# contbrd.net
KiCad netlist of a schematic drawn in EAGLE
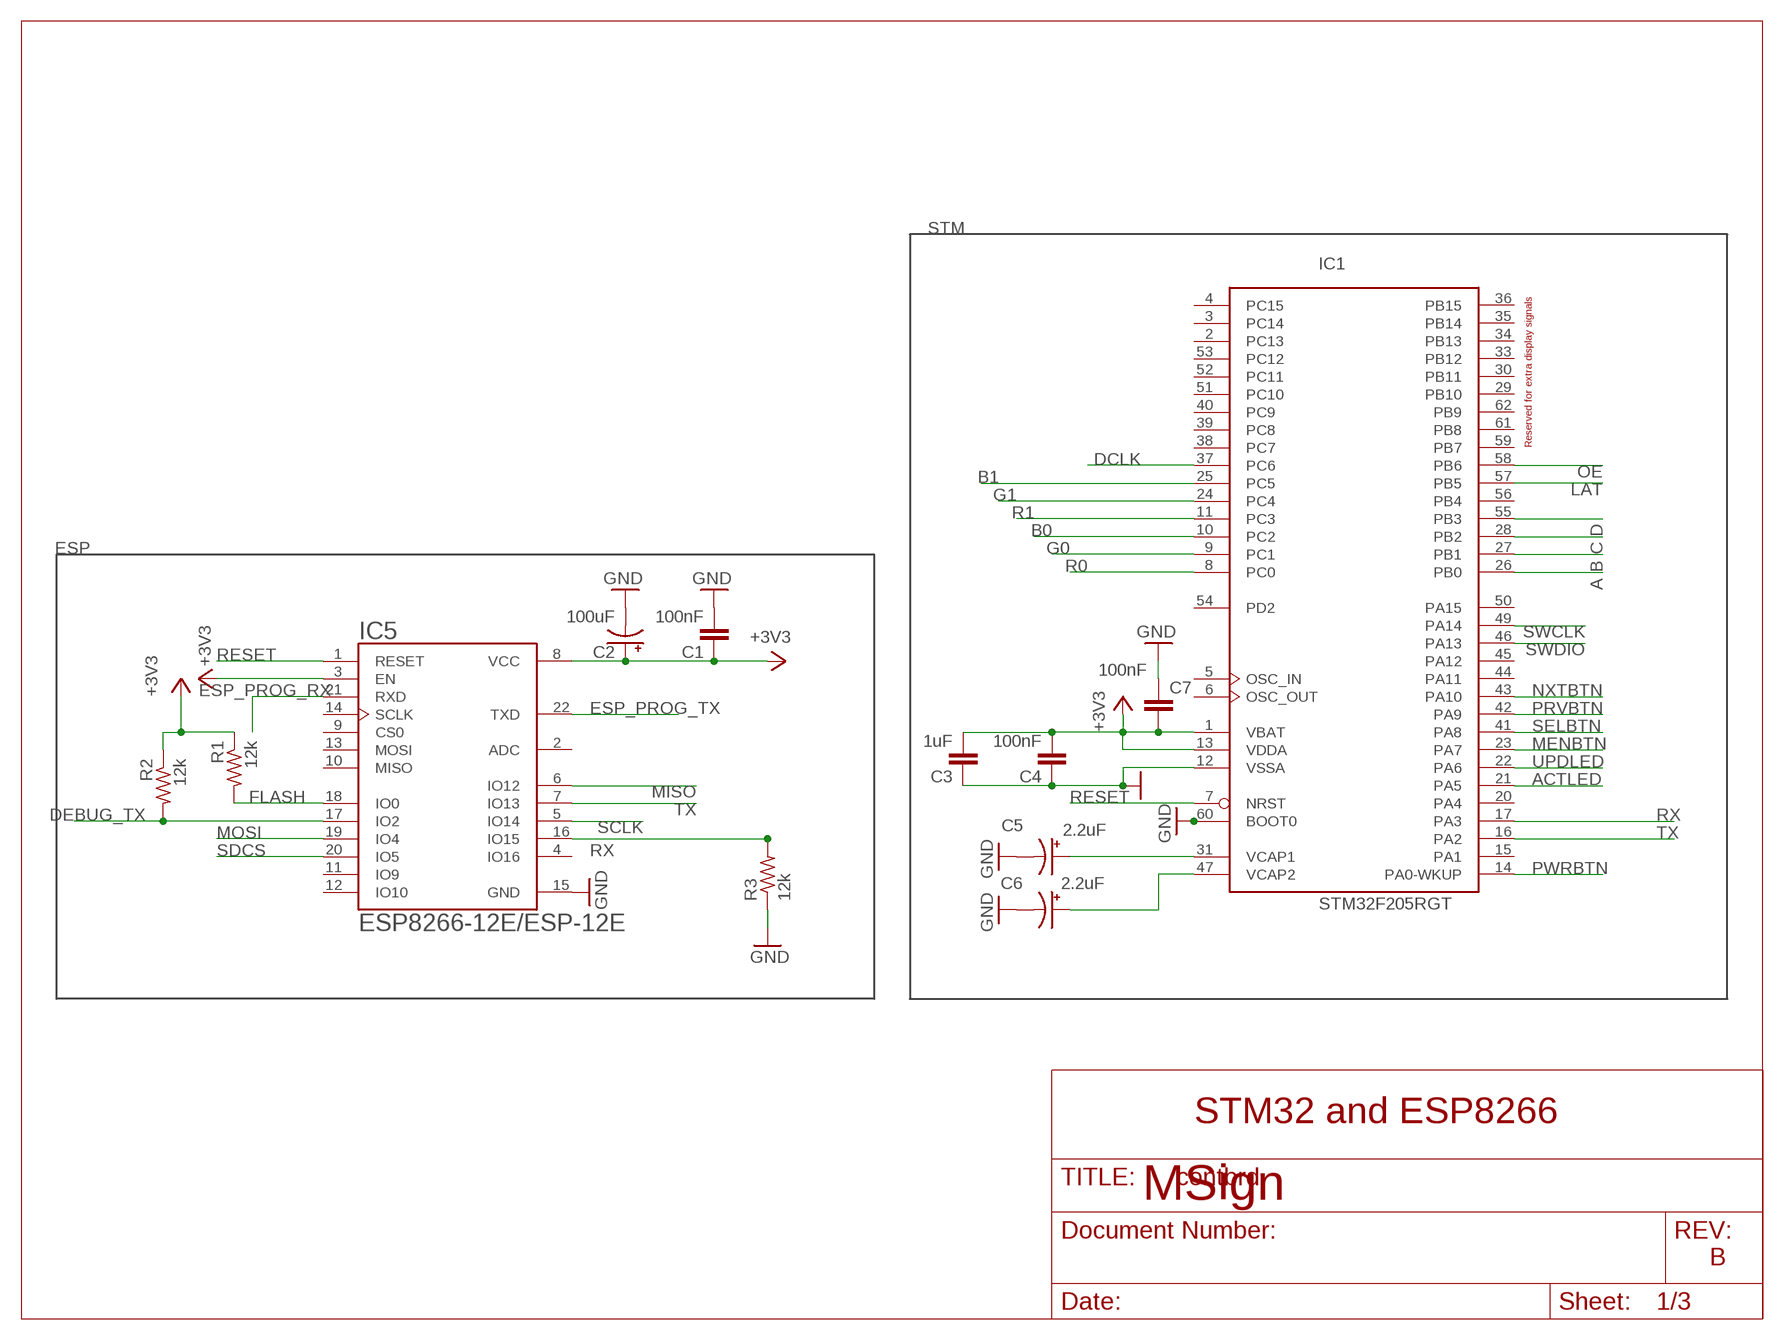
[diagram p0: schematic, sheet 1]
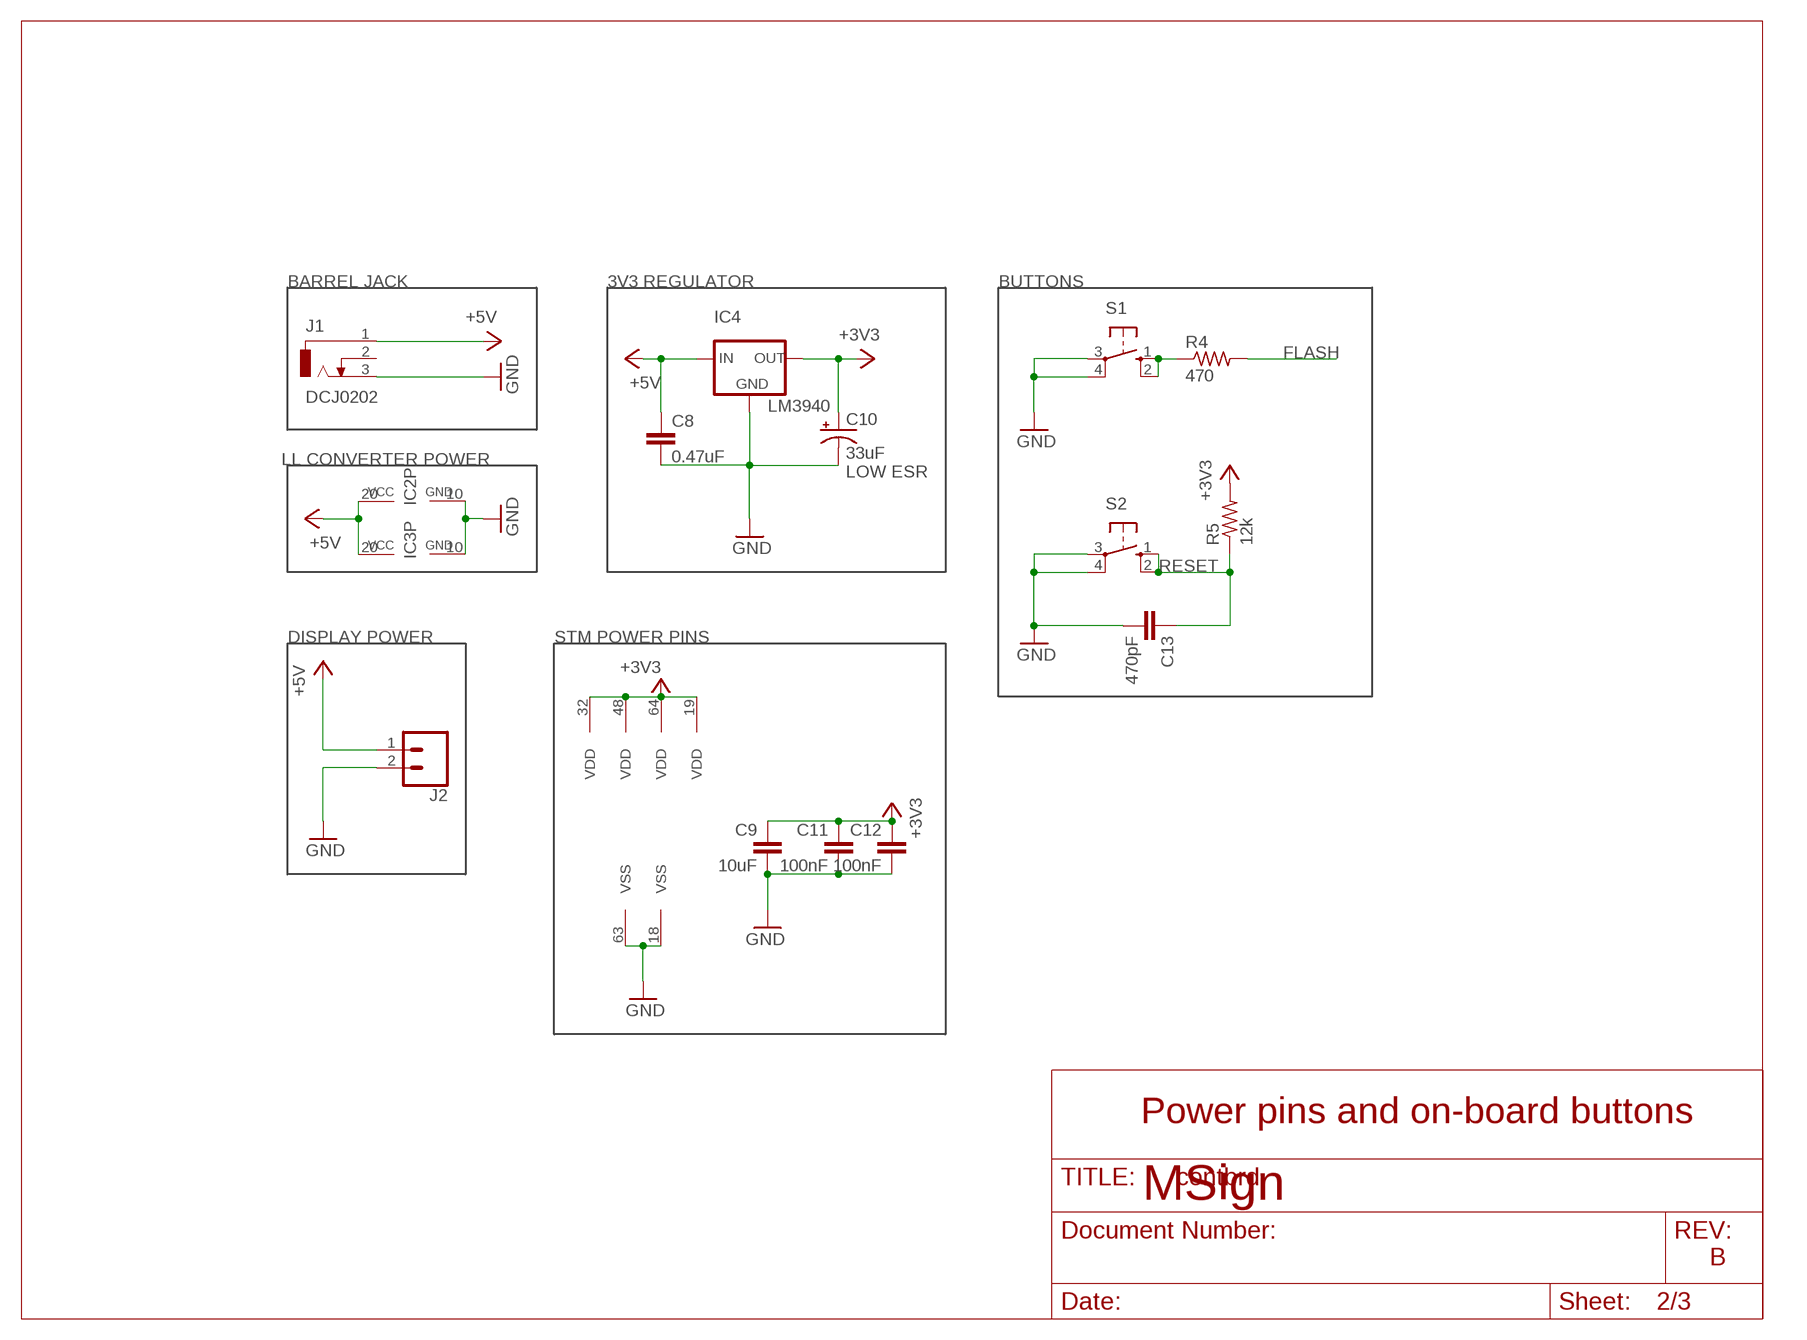
[diagram p1: schematic, sheet 2]
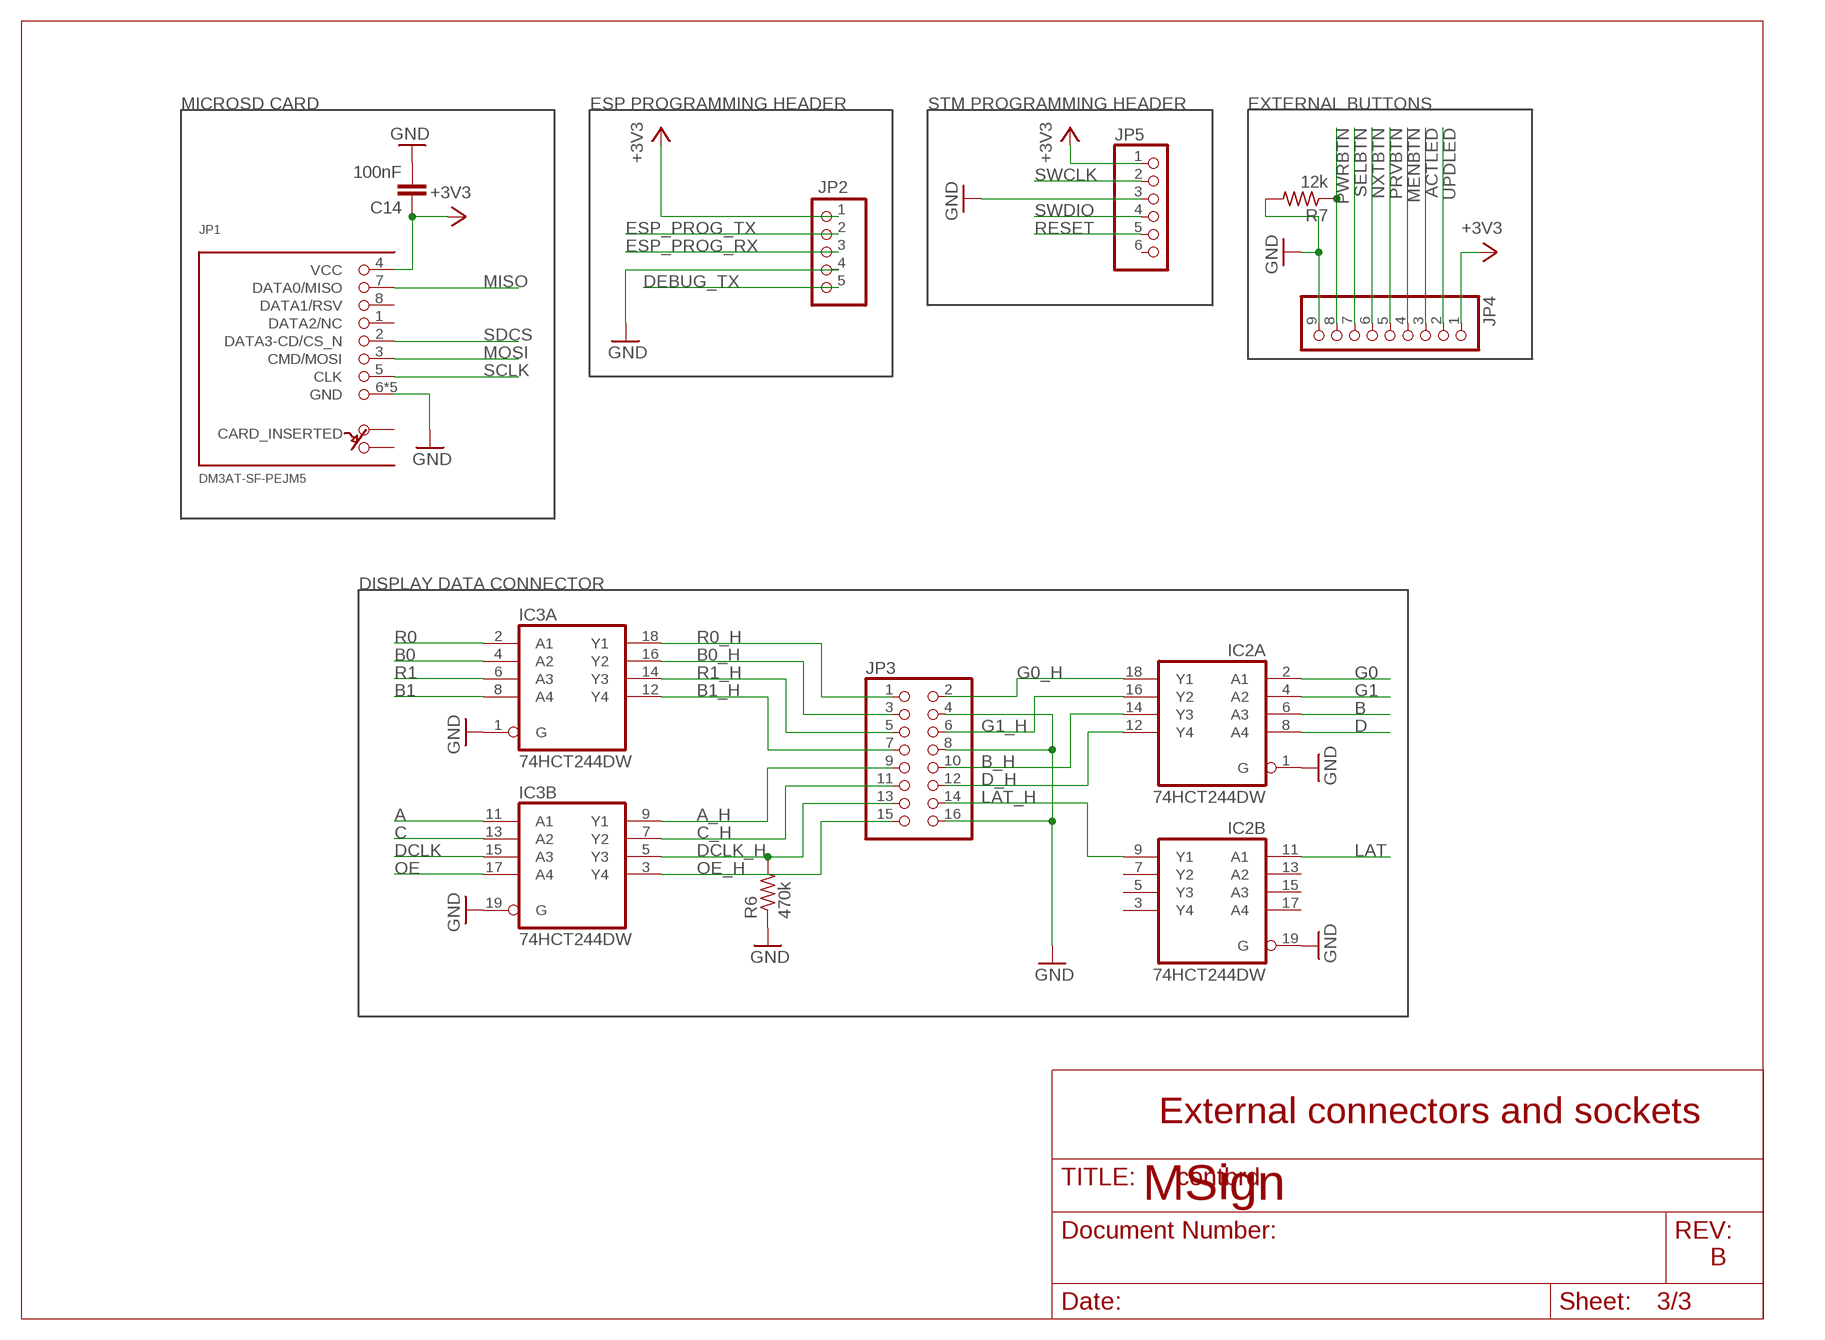
[diagram p2: schematic, sheet 3]

(export (version "E")
  (design (tool "Eeschema 10.0.6"))
  (components
    (comp (ref "C14")
      (value "100nF")
      (footprint "eagle-import:C025-025X050")
      (libsource (lib "eagle-import") (part "C-EU025-025X050"))
    )
    (comp (ref "IC2")
      (value "74HCT244DW")
      (footprint "eagle-import:SO20W")
      (libsource (lib "eagle-import") (part "74244DWHCT"))
    )
    (comp (ref "IC3")
      (value "74HCT244DW")
      (footprint "eagle-import:SO20W")
      (libsource (lib "eagle-import") (part "74244DWHCT"))
    )
    (comp (ref "JP1")
      (value "DM3AT-SF-PEJM5")
      (footprint "eagle-import:DM3AT-SF-PEJM5")
      (fields (field (name "MANUFACTURER") "Hirose Electric Co Ltd"))
      (libsource (lib "eagle-import") (part "DM3AT-SF-PEJM5"))
    )
    (comp (ref "JP2")
      (value "PINHD-1X5")
      (footprint "eagle-import:1X05")
      (libsource (lib "eagle-import") (part "PINHD-1X5"))
    )
    (comp (ref "JP3")
      (value "PINHD-2X8")
      (footprint "eagle-import:2X08")
      (libsource (lib "eagle-import") (part "PINHD-2X8"))
    )
    (comp (ref "JP4")
      (value "PINHD-1X9")
      (footprint "eagle-import:1X09")
      (libsource (lib "eagle-import") (part "PINHD-1X9"))
    )
    (comp (ref "JP5")
      (value "PINHD-1X6")
      (footprint "eagle-import:1X06")
      (libsource (lib "eagle-import") (part "PINHD-1X6"))
    )
    (comp (ref "R6")
      (value "470k")
      (footprint "eagle-import:0204_7")
      (libsource (lib "eagle-import") (part "R-US_0204/7"))
    )
    (comp (ref "R7")
      (value "12k")
      (footprint "eagle-import:0204_7")
      (libsource (lib "eagle-import") (part "R-US_0204/7"))
    )
    (comp (ref "C8")
      (value "0.47uF")
      (footprint "eagle-import:C050-024X044")
      (libsource (lib "eagle-import") (part "C-EU050-024X044"))
    )
    (comp (ref "C9")
      (value "10uF")
      (footprint "eagle-import:C025-025X050")
      (libsource (lib "eagle-import") (part "C-EU025-025X050"))
    )
    (comp (ref "C10")
      (value "33uF")
      (footprint "eagle-import:E2-5")
      (libsource (lib "eagle-import") (part "CPOL-USE2-5"))
    )
    (comp (ref "C11")
      (value "100nF")
      (footprint "eagle-import:C025-025X050")
      (libsource (lib "eagle-import") (part "C-EU025-025X050"))
    )
    (comp (ref "C12")
      (value "100nF")
      (footprint "eagle-import:C025-025X050")
      (libsource (lib "eagle-import") (part "C-EU025-025X050"))
    )
    (comp (ref "C13")
      (value "470pF")
      (footprint "eagle-import:C025-025X050")
      (libsource (lib "eagle-import") (part "C-EU025-025X050"))
    )
    (comp (ref "IC1")
      (value "STM32F205RGT")
      (footprint "eagle-import:LQFP64")
      (libsource (lib "eagle-import") (part "STM32F205RTG"))
    )
    (comp (ref "IC4")
      (value "LM3940")
      (footprint "eagle-import:TO220")
      (fields (field (name "MF") "Texas Instruments"))
      (libsource (lib "eagle-import") (part "LM3940"))
    )
    (comp (ref "J1")
      (value "DCJ0202")
      (footprint "eagle-import:DCJ0202")
      (libsource (lib "eagle-import") (part "DCJ0202"))
    )
    (comp (ref "J2")
      (value "CONN_025MM")
      (footprint "eagle-import:SCREWTERMINAL-5MM-2")
      (libsource (lib "eagle-import") (part "CONN_025MM"))
    )
    (comp (ref "R4")
      (value "470")
      (footprint "eagle-import:0204_7")
      (libsource (lib "eagle-import") (part "R-US_0204/7"))
    )
    (comp (ref "R5")
      (value "12k")
      (footprint "eagle-import:0204_7")
      (libsource (lib "eagle-import") (part "R-US_0204/7"))
    )
    (comp (ref "S1")
      (value "10-XX")
      (footprint "eagle-import:B3F-10XX")
      (fields (field (name "MPN") "B3F-1000"))
      (libsource (lib "eagle-import") (part "10-XX"))
    )
    (comp (ref "S2")
      (value "10-XX")
      (footprint "eagle-import:B3F-10XX")
      (fields (field (name "MPN") "B3F-1000"))
      (libsource (lib "eagle-import") (part "10-XX"))
    )
    (comp (ref "C1")
      (value "100nF")
      (footprint "eagle-import:C025-025X050")
      (libsource (lib "eagle-import") (part "C-EU025-025X050"))
    )
    (comp (ref "C2")
      (value "100uF")
      (footprint "eagle-import:E2,5-6")
      (libsource (lib "eagle-import") (part "CPOL-USE2.5-6"))
    )
    (comp (ref "C3")
      (value "1uF")
      (footprint "eagle-import:C050-024X044")
      (libsource (lib "eagle-import") (part "C-EU050-024X044"))
    )
    (comp (ref "C4")
      (value "100nF")
      (footprint "eagle-import:C025-025X050")
      (libsource (lib "eagle-import") (part "C-EU025-025X050"))
    )
    (comp (ref "C5")
      (value "2.2uF")
      (footprint "eagle-import:E1,8-4")
      (libsource (lib "eagle-import") (part "CPOL-USE1.8-4"))
    )
    (comp (ref "C6")
      (value "2.2uF")
      (footprint "eagle-import:E1,8-4")
      (libsource (lib "eagle-import") (part "CPOL-USE1.8-4"))
    )
    (comp (ref "C7")
      (value "100nF")
      (footprint "eagle-import:C025-025X050")
      (libsource (lib "eagle-import") (part "C-EU025-025X050"))
    )
    (comp (ref "IC5")
      (value "ESP8266-12E/ESP-12E")
      (footprint "eagle-import:XCVR_ESP8266-12E_ESP-12E")
      (fields (field (name "MF") "AI-Thinker"))
      (libsource (lib "eagle-import") (part "ESP8266-12E/ESP-12E"))
    )
    (comp (ref "R1")
      (value "12k")
      (footprint "eagle-import:0204_7")
      (libsource (lib "eagle-import") (part "R-US_0204/7"))
    )
    (comp (ref "R2")
      (value "12k")
      (footprint "eagle-import:0204_7")
      (libsource (lib "eagle-import") (part "R-US_0204/7"))
    )
    (comp (ref "R3")
      (value "12k")
      (footprint "eagle-import:0204_7")
      (libsource (lib "eagle-import") (part "R-US_0204/7"))
    )
  )
  (nets
    (net (code "1") (name "+3V3") (class "Default")
      (node (ref "C1") (pin "1") (pinfunction "1_1") (pintype "passive"))
      (node (ref "C10") (pin "+") (pinfunction "+_+") (pintype "passive"))
      (node (ref "C11") (pin "1") (pinfunction "1_1") (pintype "passive"))
      (node (ref "C12") (pin "1") (pinfunction "1_1") (pintype "passive"))
      (node (ref "C14") (pin "1") (pinfunction "1_1") (pintype "passive"))
      (node (ref "C2") (pin "+") (pinfunction "+_+") (pintype "passive"))
      (node (ref "C3") (pin "2") (pinfunction "2_2") (pintype "passive"))
      (node (ref "C4") (pin "2") (pinfunction "2_2") (pintype "passive"))
      (node (ref "C7") (pin "2") (pinfunction "2_2") (pintype "passive"))
      (node (ref "C9") (pin "1") (pinfunction "1_1") (pintype "passive"))
      (node (ref "IC1") (pin "1") (pinfunction "VBAT_1") (pintype "power_in"))
      (node (ref "IC1") (pin "13") (pinfunction "VDDA_13") (pintype "power_in"))
      (node (ref "IC1") (pin "19") (pinfunction "VDD_19") (pintype "power_in"))
      (node (ref "IC1") (pin "32") (pinfunction "VDD_32") (pintype "power_in"))
      (node (ref "IC1") (pin "48") (pinfunction "VDD_48") (pintype "power_in"))
      (node (ref "IC1") (pin "64") (pinfunction "VDD_64") (pintype "power_in"))
      (node (ref "IC4") (pin "3") (pinfunction "OUT_3") (pintype "output"))
      (node (ref "IC5") (pin "3") (pinfunction "EN_3") (pintype "input"))
      (node (ref "IC5") (pin "8") (pinfunction "VCC_8") (pintype "power_in"))
      (node (ref "JP1") (pin "4") (pinfunction "VCC_4") (pintype "bidirectional"))
      (node (ref "JP2") (pin "1") (pinfunction "1_1") (pintype "passive"))
      (node (ref "JP4") (pin "1") (pinfunction "1_1") (pintype "passive"))
      (node (ref "JP5") (pin "1") (pinfunction "1_1") (pintype "passive"))
      (node (ref "R1") (pin "1") (pinfunction "1_1") (pintype "passive"))
      (node (ref "R2") (pin "1") (pinfunction "1_1") (pintype "passive"))
      (node (ref "R5") (pin "2") (pinfunction "2_2") (pintype "passive"))
    )
    (net (code "2") (name "+5V") (class "Default")
      (node (ref "C8") (pin "1") (pinfunction "1_1") (pintype "passive"))
      (node (ref "IC2") (pin "20") (pinfunction "VCC_20") (pintype "power_in"))
      (node (ref "IC3") (pin "20") (pinfunction "VCC_20") (pintype "power_in"))
      (node (ref "IC4") (pin "1") (pinfunction "IN_1") (pintype "input"))
      (node (ref "J1") (pin "1") (pinfunction "1_1") (pintype "passive"))
      (node (ref "J2") (pin "1") (pinfunction "1_1") (pintype "passive"))
    )
    (net (code "3") (name "A") (class "Default")
      (node (ref "IC1") (pin "26") (pinfunction "PB0_26") (pintype "bidirectional"))
      (node (ref "IC3") (pin "11") (pinfunction "A1_11") (pintype "input"))
    )
    (net (code "4") (name "ACTLED") (class "Default")
      (node (ref "IC1") (pin "21") (pinfunction "PA5_21") (pintype "bidirectional"))
      (node (ref "JP4") (pin "3") (pinfunction "3_3") (pintype "passive"))
    )
    (net (code "5") (name "A_H") (class "Default")
      (node (ref "IC3") (pin "9") (pinfunction "Y1_9") (pintype "tri_state"))
      (node (ref "JP3") (pin "9") (pinfunction "9_9") (pintype "passive"))
    )
    (net (code "6") (name "B") (class "Default")
      (node (ref "IC1") (pin "27") (pinfunction "PB1_27") (pintype "bidirectional"))
      (node (ref "IC2") (pin "6") (pinfunction "A3_6") (pintype "input"))
    )
    (net (code "7") (name "B0") (class "Default")
      (node (ref "IC1") (pin "10") (pinfunction "PC2_10") (pintype "bidirectional"))
      (node (ref "IC3") (pin "4") (pinfunction "A2_4") (pintype "input"))
    )
    (net (code "8") (name "B0_H") (class "Default")
      (node (ref "IC3") (pin "16") (pinfunction "Y2_16") (pintype "tri_state"))
      (node (ref "JP3") (pin "3") (pinfunction "3_3") (pintype "passive"))
    )
    (net (code "9") (name "B1") (class "Default")
      (node (ref "IC1") (pin "25") (pinfunction "PC5_25") (pintype "bidirectional"))
      (node (ref "IC3") (pin "8") (pinfunction "A4_8") (pintype "input"))
    )
    (net (code "10") (name "B1_H") (class "Default")
      (node (ref "IC3") (pin "12") (pinfunction "Y4_12") (pintype "tri_state"))
      (node (ref "JP3") (pin "7") (pinfunction "7_7") (pintype "passive"))
    )
    (net (code "11") (name "B_H") (class "Default")
      (node (ref "IC2") (pin "14") (pinfunction "Y3_14") (pintype "tri_state"))
      (node (ref "JP3") (pin "10") (pinfunction "10_10") (pintype "passive"))
    )
    (net (code "12") (name "C") (class "Default")
      (node (ref "IC1") (pin "28") (pinfunction "PB2_28") (pintype "bidirectional"))
      (node (ref "IC3") (pin "13") (pinfunction "A2_13") (pintype "input"))
    )
    (net (code "13") (name "C_H") (class "Default")
      (node (ref "IC3") (pin "7") (pinfunction "Y2_7") (pintype "tri_state"))
      (node (ref "JP3") (pin "11") (pinfunction "11_11") (pintype "passive"))
    )
    (net (code "14") (name "D") (class "Default")
      (node (ref "IC1") (pin "55") (pinfunction "PB3_55") (pintype "bidirectional"))
      (node (ref "IC2") (pin "8") (pinfunction "A4_8") (pintype "input"))
    )
    (net (code "15") (name "DCLK") (class "Default")
      (node (ref "IC1") (pin "37") (pinfunction "PC6_37") (pintype "bidirectional"))
      (node (ref "IC3") (pin "15") (pinfunction "A3_15") (pintype "input"))
    )
    (net (code "16") (name "DCLK_H") (class "Default")
      (node (ref "IC3") (pin "5") (pinfunction "Y3_5") (pintype "tri_state"))
      (node (ref "JP3") (pin "13") (pinfunction "13_13") (pintype "passive"))
      (node (ref "R6") (pin "2") (pinfunction "2_2") (pintype "passive"))
    )
    (net (code "17") (name "DEBUG_TX") (class "Default")
      (node (ref "IC5") (pin "17") (pinfunction "IO2_17") (pintype "bidirectional"))
      (node (ref "JP2") (pin "5") (pinfunction "5_5") (pintype "passive"))
      (node (ref "R2") (pin "2") (pinfunction "2_2") (pintype "passive"))
    )
    (net (code "18") (name "D_H") (class "Default")
      (node (ref "IC2") (pin "12") (pinfunction "Y4_12") (pintype "tri_state"))
      (node (ref "JP3") (pin "12") (pinfunction "12_12") (pintype "passive"))
    )
    (net (code "19") (name "ESP_PROG_RX") (class "Default")
      (node (ref "IC5") (pin "21") (pinfunction "RXD_21") (pintype "input"))
      (node (ref "JP2") (pin "3") (pinfunction "3_3") (pintype "passive"))
    )
    (net (code "20") (name "ESP_PROG_TX") (class "Default")
      (node (ref "IC5") (pin "22") (pinfunction "TXD_22") (pintype "output"))
      (node (ref "JP2") (pin "2") (pinfunction "2_2") (pintype "passive"))
    )
    (net (code "21") (name "FLASH") (class "Default")
      (node (ref "IC5") (pin "18") (pinfunction "IO0_18") (pintype "bidirectional"))
      (node (ref "R1") (pin "2") (pinfunction "2_2") (pintype "passive"))
      (node (ref "R4") (pin "2") (pinfunction "2_2") (pintype "passive"))
    )
    (net (code "22") (name "G0") (class "Default")
      (node (ref "IC1") (pin "9") (pinfunction "PC1_9") (pintype "bidirectional"))
      (node (ref "IC2") (pin "2") (pinfunction "A1_2") (pintype "input"))
    )
    (net (code "23") (name "G0_H") (class "Default")
      (node (ref "IC2") (pin "18") (pinfunction "Y1_18") (pintype "tri_state"))
      (node (ref "JP3") (pin "2") (pinfunction "2_2") (pintype "passive"))
    )
    (net (code "24") (name "G1") (class "Default")
      (node (ref "IC1") (pin "24") (pinfunction "PC4_24") (pintype "bidirectional"))
      (node (ref "IC2") (pin "4") (pinfunction "A2_4") (pintype "input"))
    )
    (net (code "25") (name "G1_H") (class "Default")
      (node (ref "IC2") (pin "16") (pinfunction "Y2_16") (pintype "tri_state"))
      (node (ref "JP3") (pin "6") (pinfunction "6_6") (pintype "passive"))
    )
    (net (code "26") (name "GND") (class "Default")
      (node (ref "C1") (pin "2") (pinfunction "2_2") (pintype "passive"))
      (node (ref "C10") (pin "-") (pinfunction "-_-") (pintype "passive"))
      (node (ref "C11") (pin "2") (pinfunction "2_2") (pintype "passive"))
      (node (ref "C12") (pin "2") (pinfunction "2_2") (pintype "passive"))
      (node (ref "C13") (pin "2") (pinfunction "2_2") (pintype "passive"))
      (node (ref "C14") (pin "2") (pinfunction "2_2") (pintype "passive"))
      (node (ref "C2") (pin "-") (pinfunction "-_-") (pintype "passive"))
      (node (ref "C3") (pin "1") (pinfunction "1_1") (pintype "passive"))
      (node (ref "C4") (pin "1") (pinfunction "1_1") (pintype "passive"))
      (node (ref "C5") (pin "-") (pinfunction "-_-") (pintype "passive"))
      (node (ref "C6") (pin "-") (pinfunction "-_-") (pintype "passive"))
      (node (ref "C7") (pin "1") (pinfunction "1_1") (pintype "passive"))
      (node (ref "C8") (pin "2") (pinfunction "2_2") (pintype "passive"))
      (node (ref "C9") (pin "2") (pinfunction "2_2") (pintype "passive"))
      (node (ref "IC1") (pin "12") (pinfunction "VSSA_12") (pintype "power_in"))
      (node (ref "IC1") (pin "18") (pinfunction "VSS_18") (pintype "power_in"))
      (node (ref "IC1") (pin "60") (pinfunction "BOOT0_60") (pintype "input"))
      (node (ref "IC1") (pin "63") (pinfunction "VSS_63") (pintype "power_in"))
      (node (ref "IC2") (pin "1") (pinfunction "G_1") (pintype "input"))
      (node (ref "IC2") (pin "10") (pinfunction "GND_10") (pintype "power_in"))
      (node (ref "IC2") (pin "19") (pinfunction "G_19") (pintype "input"))
      (node (ref "IC3") (pin "1") (pinfunction "G_1") (pintype "input"))
      (node (ref "IC3") (pin "10") (pinfunction "GND_10") (pintype "power_in"))
      (node (ref "IC3") (pin "19") (pinfunction "G_19") (pintype "input"))
      (node (ref "IC4") (pin "2") (pinfunction "GND_2") (pintype "input"))
      (node (ref "IC5") (pin "15") (pinfunction "GND_15") (pintype "power_in"))
      (node (ref "J1") (pin "3") (pinfunction "3_3") (pintype "passive"))
      (node (ref "J2") (pin "2") (pinfunction "2_2") (pintype "passive"))
      (node (ref "JP1") (pin "6") (pinfunction "GND_6") (pintype "bidirectional"))
      (node (ref "JP1") (pin "MOUNT0") (pinfunction "GND_MOUNT0") (pintype "bidirectional"))
      (node (ref "JP1") (pin "MOUNT1") (pinfunction "GND_MOUNT1") (pintype "bidirectional"))
      (node (ref "JP1") (pin "MOUNT2") (pinfunction "GND_MOUNT2") (pintype "bidirectional"))
      (node (ref "JP1") (pin "MOUNT3") (pinfunction "GND_MOUNT3") (pintype "bidirectional"))
      (node (ref "JP2") (pin "4") (pinfunction "4_4") (pintype "passive"))
      (node (ref "JP3") (pin "16") (pinfunction "16_16") (pintype "passive"))
      (node (ref "JP3") (pin "4") (pinfunction "4_4") (pintype "passive"))
      (node (ref "JP3") (pin "8") (pinfunction "8_8") (pintype "passive"))
      (node (ref "JP4") (pin "9") (pinfunction "9_9") (pintype "passive"))
      (node (ref "JP5") (pin "3") (pinfunction "3_3") (pintype "passive"))
      (node (ref "R3") (pin "1") (pinfunction "1_1") (pintype "passive"))
      (node (ref "R6") (pin "1") (pinfunction "1_1") (pintype "passive"))
      (node (ref "R7") (pin "2") (pinfunction "2_2") (pintype "passive"))
      (node (ref "S1") (pin "3") (pinfunction "P_3") (pintype "passive"))
      (node (ref "S1") (pin "4") (pinfunction "P1_4") (pintype "passive"))
      (node (ref "S2") (pin "3") (pinfunction "P_3") (pintype "passive"))
      (node (ref "S2") (pin "4") (pinfunction "P1_4") (pintype "passive"))
    )
    (net (code "27") (name "LAT") (class "Default")
      (node (ref "IC1") (pin "57") (pinfunction "PB5_57") (pintype "bidirectional"))
      (node (ref "IC2") (pin "11") (pinfunction "A1_11") (pintype "input"))
    )
    (net (code "28") (name "LAT_H") (class "Default")
      (node (ref "IC2") (pin "9") (pinfunction "Y1_9") (pintype "tri_state"))
      (node (ref "JP3") (pin "14") (pinfunction "14_14") (pintype "passive"))
    )
    (net (code "29") (name "MENBTN") (class "Default")
      (node (ref "IC1") (pin "23") (pinfunction "PA7_23") (pintype "bidirectional"))
      (node (ref "JP4") (pin "4") (pinfunction "4_4") (pintype "passive"))
    )
    (net (code "30") (name "MISO") (class "Default")
      (node (ref "IC5") (pin "6") (pinfunction "IO12_6") (pintype "bidirectional"))
      (node (ref "JP1") (pin "7") (pinfunction "DATA0/MISO_7") (pintype "bidirectional"))
    )
    (net (code "31") (name "MOSI") (class "Default")
      (node (ref "IC5") (pin "19") (pinfunction "IO4_19") (pintype "bidirectional"))
      (node (ref "JP1") (pin "3") (pinfunction "CMD/MOSI_3") (pintype "bidirectional"))
    )
    (net (code "32") (name "NXTBTN") (class "Default")
      (node (ref "IC1") (pin "43") (pinfunction "PA10_43") (pintype "bidirectional"))
      (node (ref "JP4") (pin "6") (pinfunction "6_6") (pintype "passive"))
    )
    (net (code "33") (name "Net-(IC1A-VCAP1)") (class "Default")
      (node (ref "C5") (pin "+") (pinfunction "+_+") (pintype "passive"))
      (node (ref "IC1") (pin "31") (pinfunction "VCAP1_31") (pintype "power_in"))
    )
    (net (code "34") (name "Net-(IC1A-VCAP2)") (class "Default")
      (node (ref "C6") (pin "+") (pinfunction "+_+") (pintype "passive"))
      (node (ref "IC1") (pin "47") (pinfunction "VCAP2_47") (pintype "power_in"))
    )
    (net (code "35") (name "Net-(S1-S)") (class "Default")
      (node (ref "R4") (pin "1") (pinfunction "1_1") (pintype "passive"))
      (node (ref "S1") (pin "1") (pinfunction "S_1") (pintype "passive"))
      (node (ref "S1") (pin "2") (pinfunction "S1_2") (pintype "passive"))
    )
    (net (code "36") (name "OE") (class "Default")
      (node (ref "IC1") (pin "58") (pinfunction "PB6_58") (pintype "bidirectional"))
      (node (ref "IC3") (pin "17") (pinfunction "A4_17") (pintype "input"))
    )
    (net (code "37") (name "OE_H") (class "Default")
      (node (ref "IC3") (pin "3") (pinfunction "Y4_3") (pintype "tri_state"))
      (node (ref "JP3") (pin "15") (pinfunction "15_15") (pintype "passive"))
    )
    (net (code "38") (name "PRVBTN") (class "Default")
      (node (ref "IC1") (pin "42") (pinfunction "PA9_42") (pintype "bidirectional"))
      (node (ref "JP4") (pin "5") (pinfunction "5_5") (pintype "passive"))
    )
    (net (code "39") (name "PWRBTN") (class "Default")
      (node (ref "IC1") (pin "14") (pinfunction "PA0-WKUP_14") (pintype "bidirectional"))
      (node (ref "JP4") (pin "8") (pinfunction "8_8") (pintype "passive"))
      (node (ref "R7") (pin "1") (pinfunction "1_1") (pintype "passive"))
    )
    (net (code "40") (name "R0") (class "Default")
      (node (ref "IC1") (pin "8") (pinfunction "PC0_8") (pintype "bidirectional"))
      (node (ref "IC3") (pin "2") (pinfunction "A1_2") (pintype "input"))
    )
    (net (code "41") (name "R0_H") (class "Default")
      (node (ref "IC3") (pin "18") (pinfunction "Y1_18") (pintype "tri_state"))
      (node (ref "JP3") (pin "1") (pinfunction "1_1") (pintype "passive"))
    )
    (net (code "42") (name "R1") (class "Default")
      (node (ref "IC1") (pin "11") (pinfunction "PC3_11") (pintype "bidirectional"))
      (node (ref "IC3") (pin "6") (pinfunction "A3_6") (pintype "input"))
    )
    (net (code "43") (name "R1_H") (class "Default")
      (node (ref "IC3") (pin "14") (pinfunction "Y3_14") (pintype "tri_state"))
      (node (ref "JP3") (pin "5") (pinfunction "5_5") (pintype "passive"))
    )
    (net (code "44") (name "RESET") (class "Default")
      (node (ref "C13") (pin "1") (pinfunction "1_1") (pintype "passive"))
      (node (ref "IC1") (pin "7") (pinfunction "NRST_7") (pintype "bidirectional"))
      (node (ref "IC5") (pin "1") (pinfunction "RESET_1") (pintype "input"))
      (node (ref "JP5") (pin "5") (pinfunction "5_5") (pintype "passive"))
      (node (ref "R5") (pin "1") (pinfunction "1_1") (pintype "passive"))
      (node (ref "S2") (pin "1") (pinfunction "S_1") (pintype "passive"))
      (node (ref "S2") (pin "2") (pinfunction "S1_2") (pintype "passive"))
    )
    (net (code "45") (name "RX") (class "Default")
      (node (ref "IC1") (pin "17") (pinfunction "PA3_17") (pintype "bidirectional"))
      (node (ref "IC5") (pin "16") (pinfunction "IO15_16") (pintype "bidirectional"))
      (node (ref "R3") (pin "2") (pinfunction "2_2") (pintype "passive"))
    )
    (net (code "46") (name "SCLK") (class "Default")
      (node (ref "IC5") (pin "5") (pinfunction "IO14_5") (pintype "bidirectional"))
      (node (ref "JP1") (pin "5") (pinfunction "CLK_5") (pintype "bidirectional"))
    )
    (net (code "47") (name "SDCS") (class "Default")
      (node (ref "IC5") (pin "20") (pinfunction "IO5_20") (pintype "bidirectional"))
      (node (ref "JP1") (pin "2") (pinfunction "DATA3-CD/CS_N_2") (pintype "bidirectional"))
    )
    (net (code "48") (name "SELBTN") (class "Default")
      (node (ref "IC1") (pin "41") (pinfunction "PA8_41") (pintype "bidirectional"))
      (node (ref "JP4") (pin "7") (pinfunction "7_7") (pintype "passive"))
    )
    (net (code "49") (name "SWCLK") (class "Default")
      (node (ref "IC1") (pin "49") (pinfunction "PA14_49") (pintype "bidirectional"))
      (node (ref "JP5") (pin "2") (pinfunction "2_2") (pintype "passive"))
    )
    (net (code "50") (name "SWDIO") (class "Default")
      (node (ref "IC1") (pin "46") (pinfunction "PA13_46") (pintype "bidirectional"))
      (node (ref "JP5") (pin "4") (pinfunction "4_4") (pintype "passive"))
    )
    (net (code "51") (name "TX") (class "Default")
      (node (ref "IC1") (pin "16") (pinfunction "PA2_16") (pintype "bidirectional"))
      (node (ref "IC5") (pin "7") (pinfunction "IO13_7") (pintype "bidirectional"))
    )
    (net (code "52") (name "UPDLED") (class "Default")
      (node (ref "IC1") (pin "22") (pinfunction "PA6_22") (pintype "bidirectional"))
      (node (ref "JP4") (pin "2") (pinfunction "2_2") (pintype "passive"))
    )
    (net (code "53") (name "unconnected-(IC1A-OSC_IN-Pad5)") (class "Default")
      (node (ref "IC1") (pin "5") (pinfunction "OSC_IN_5") (pintype "bidirectional"))
    )
    (net (code "54") (name "unconnected-(IC1A-OSC_OUT-Pad6)") (class "Default")
      (node (ref "IC1") (pin "6") (pinfunction "OSC_OUT_6") (pintype "bidirectional"))
    )
    (net (code "55") (name "unconnected-(IC1A-PA1-Pad15)") (class "Default")
      (node (ref "IC1") (pin "15") (pinfunction "PA1_15") (pintype "bidirectional"))
    )
    (net (code "56") (name "unconnected-(IC1A-PA4-Pad20)") (class "Default")
      (node (ref "IC1") (pin "20") (pinfunction "PA4_20") (pintype "bidirectional"))
    )
    (net (code "57") (name "unconnected-(IC1A-PA11-Pad44)") (class "Default")
      (node (ref "IC1") (pin "44") (pinfunction "PA11_44") (pintype "bidirectional"))
    )
    (net (code "58") (name "unconnected-(IC1A-PA12-Pad45)") (class "Default")
      (node (ref "IC1") (pin "45") (pinfunction "PA12_45") (pintype "bidirectional"))
    )
    (net (code "59") (name "unconnected-(IC1A-PA15-Pad50)") (class "Default")
      (node (ref "IC1") (pin "50") (pinfunction "PA15_50") (pintype "bidirectional"))
    )
    (net (code "60") (name "unconnected-(IC1A-PB4-Pad56)") (class "Default")
      (node (ref "IC1") (pin "56") (pinfunction "PB4_56") (pintype "bidirectional"))
    )
    (net (code "61") (name "unconnected-(IC1A-PB7-Pad59)") (class "Default")
      (node (ref "IC1") (pin "59") (pinfunction "PB7_59") (pintype "bidirectional"))
    )
    (net (code "62") (name "unconnected-(IC1A-PB8-Pad61)") (class "Default")
      (node (ref "IC1") (pin "61") (pinfunction "PB8_61") (pintype "bidirectional"))
    )
    (net (code "63") (name "unconnected-(IC1A-PB9-Pad62)") (class "Default")
      (node (ref "IC1") (pin "62") (pinfunction "PB9_62") (pintype "bidirectional"))
    )
    (net (code "64") (name "unconnected-(IC1A-PB10-Pad29)") (class "Default")
      (node (ref "IC1") (pin "29") (pinfunction "PB10_29") (pintype "bidirectional"))
    )
    (net (code "65") (name "unconnected-(IC1A-PB11-Pad30)") (class "Default")
      (node (ref "IC1") (pin "30") (pinfunction "PB11_30") (pintype "bidirectional"))
    )
    (net (code "66") (name "unconnected-(IC1A-PB12-Pad33)") (class "Default")
      (node (ref "IC1") (pin "33") (pinfunction "PB12_33") (pintype "bidirectional"))
    )
    (net (code "67") (name "unconnected-(IC1A-PB13-Pad34)") (class "Default")
      (node (ref "IC1") (pin "34") (pinfunction "PB13_34") (pintype "bidirectional"))
    )
    (net (code "68") (name "unconnected-(IC1A-PB14-Pad35)") (class "Default")
      (node (ref "IC1") (pin "35") (pinfunction "PB14_35") (pintype "bidirectional"))
    )
    (net (code "69") (name "unconnected-(IC1A-PB15-Pad36)") (class "Default")
      (node (ref "IC1") (pin "36") (pinfunction "PB15_36") (pintype "bidirectional"))
    )
    (net (code "70") (name "unconnected-(IC1A-PC7-Pad38)") (class "Default")
      (node (ref "IC1") (pin "38") (pinfunction "PC7_38") (pintype "bidirectional"))
    )
    (net (code "71") (name "unconnected-(IC1A-PC8-Pad39)") (class "Default")
      (node (ref "IC1") (pin "39") (pinfunction "PC8_39") (pintype "bidirectional"))
    )
    (net (code "72") (name "unconnected-(IC1A-PC9-Pad40)") (class "Default")
      (node (ref "IC1") (pin "40") (pinfunction "PC9_40") (pintype "bidirectional"))
    )
    (net (code "73") (name "unconnected-(IC1A-PC10-Pad51)") (class "Default")
      (node (ref "IC1") (pin "51") (pinfunction "PC10_51") (pintype "bidirectional"))
    )
    (net (code "74") (name "unconnected-(IC1A-PC11-Pad52)") (class "Default")
      (node (ref "IC1") (pin "52") (pinfunction "PC11_52") (pintype "bidirectional"))
    )
    (net (code "75") (name "unconnected-(IC1A-PC12-Pad53)") (class "Default")
      (node (ref "IC1") (pin "53") (pinfunction "PC12_53") (pintype "bidirectional"))
    )
    (net (code "76") (name "unconnected-(IC1A-PC13-Pad2)") (class "Default")
      (node (ref "IC1") (pin "2") (pinfunction "PC13_2") (pintype "bidirectional"))
    )
    (net (code "77") (name "unconnected-(IC1A-PC14-Pad3)") (class "Default")
      (node (ref "IC1") (pin "3") (pinfunction "PC14_3") (pintype "bidirectional"))
    )
    (net (code "78") (name "unconnected-(IC1A-PC15-Pad4)") (class "Default")
      (node (ref "IC1") (pin "4") (pinfunction "PC15_4") (pintype "bidirectional"))
    )
    (net (code "79") (name "unconnected-(IC1A-PD2-Pad54)") (class "Default")
      (node (ref "IC1") (pin "54") (pinfunction "PD2_54") (pintype "bidirectional"))
    )
    (net (code "80") (name "unconnected-(IC2B-A2-Pad13)") (class "Default")
      (node (ref "IC2") (pin "13") (pinfunction "A2_13") (pintype "input"))
    )
    (net (code "81") (name "unconnected-(IC2B-A3-Pad15)") (class "Default")
      (node (ref "IC2") (pin "15") (pinfunction "A3_15") (pintype "input"))
    )
    (net (code "82") (name "unconnected-(IC2B-A4-Pad17)") (class "Default")
      (node (ref "IC2") (pin "17") (pinfunction "A4_17") (pintype "input"))
    )
    (net (code "83") (name "unconnected-(IC2B-Y2-Pad7)") (class "Default")
      (node (ref "IC2") (pin "7") (pinfunction "Y2_7") (pintype "tri_state"))
    )
    (net (code "84") (name "unconnected-(IC2B-Y3-Pad5)") (class "Default")
      (node (ref "IC2") (pin "5") (pinfunction "Y3_5") (pintype "tri_state"))
    )
    (net (code "85") (name "unconnected-(IC2B-Y4-Pad3)") (class "Default")
      (node (ref "IC2") (pin "3") (pinfunction "Y4_3") (pintype "tri_state"))
    )
    (net (code "86") (name "unconnected-(IC5-ADC-Pad2)") (class "Default")
      (node (ref "IC5") (pin "2") (pinfunction "ADC_2") (pintype "passive"))
    )
    (net (code "87") (name "unconnected-(IC5-CS0-Pad9)") (class "Default")
      (node (ref "IC5") (pin "9") (pinfunction "CS0_9") (pintype "input"))
    )
    (net (code "88") (name "unconnected-(IC5-IO9-Pad11)") (class "Default")
      (node (ref "IC5") (pin "11") (pinfunction "IO9_11") (pintype "bidirectional"))
    )
    (net (code "89") (name "unconnected-(IC5-IO10-Pad12)") (class "Default")
      (node (ref "IC5") (pin "12") (pinfunction "IO10_12") (pintype "bidirectional"))
    )
    (net (code "90") (name "unconnected-(IC5-IO16-Pad4)") (class "Default")
      (node (ref "IC5") (pin "4") (pinfunction "IO16_4") (pintype "bidirectional"))
    )
    (net (code "91") (name "unconnected-(IC5-MISO-Pad10)") (class "Default")
      (node (ref "IC5") (pin "10") (pinfunction "MISO_10") (pintype "bidirectional"))
    )
    (net (code "92") (name "unconnected-(IC5-MOSI-Pad13)") (class "Default")
      (node (ref "IC5") (pin "13") (pinfunction "MOSI_13") (pintype "bidirectional"))
    )
    (net (code "93") (name "unconnected-(IC5-SCLK-Pad14)") (class "Default")
      (node (ref "IC5") (pin "14") (pinfunction "SCLK_14") (pintype "input"))
    )
    (net (code "94") (name "unconnected-(J1-Pad2)") (class "Default")
      (node (ref "J1") (pin "2") (pinfunction "2_2") (pintype "passive"))
    )
    (net (code "95") (name "unconnected-(JP1-DATA1{slash}RSV-Pad8)") (class "Default")
      (node (ref "JP1") (pin "8") (pinfunction "DATA1/RSV_8") (pintype "bidirectional"))
    )
    (net (code "96") (name "unconnected-(JP1-DATA2{slash}NC-Pad1)") (class "Default")
      (node (ref "JP1") (pin "1") (pinfunction "DATA2/NC_1") (pintype "bidirectional"))
    )
    (net (code "97") (name "unconnected-(JP1-PadA)") (class "Default")
      (node (ref "JP1") (pin "A") (pinfunction "A_A") (pintype "bidirectional"))
    )
    (net (code "98") (name "unconnected-(JP1-PadB)") (class "Default")
      (node (ref "JP1") (pin "B") (pinfunction "B_B") (pintype "bidirectional"))
    )
    (net (code "99") (name "unconnected-(JP5-Pad6)") (class "Default")
      (node (ref "JP5") (pin "6") (pinfunction "6_6") (pintype "passive"))
    )
  )
)
